# 884.net
KiCad netlist of a schematic drawn in EAGLE
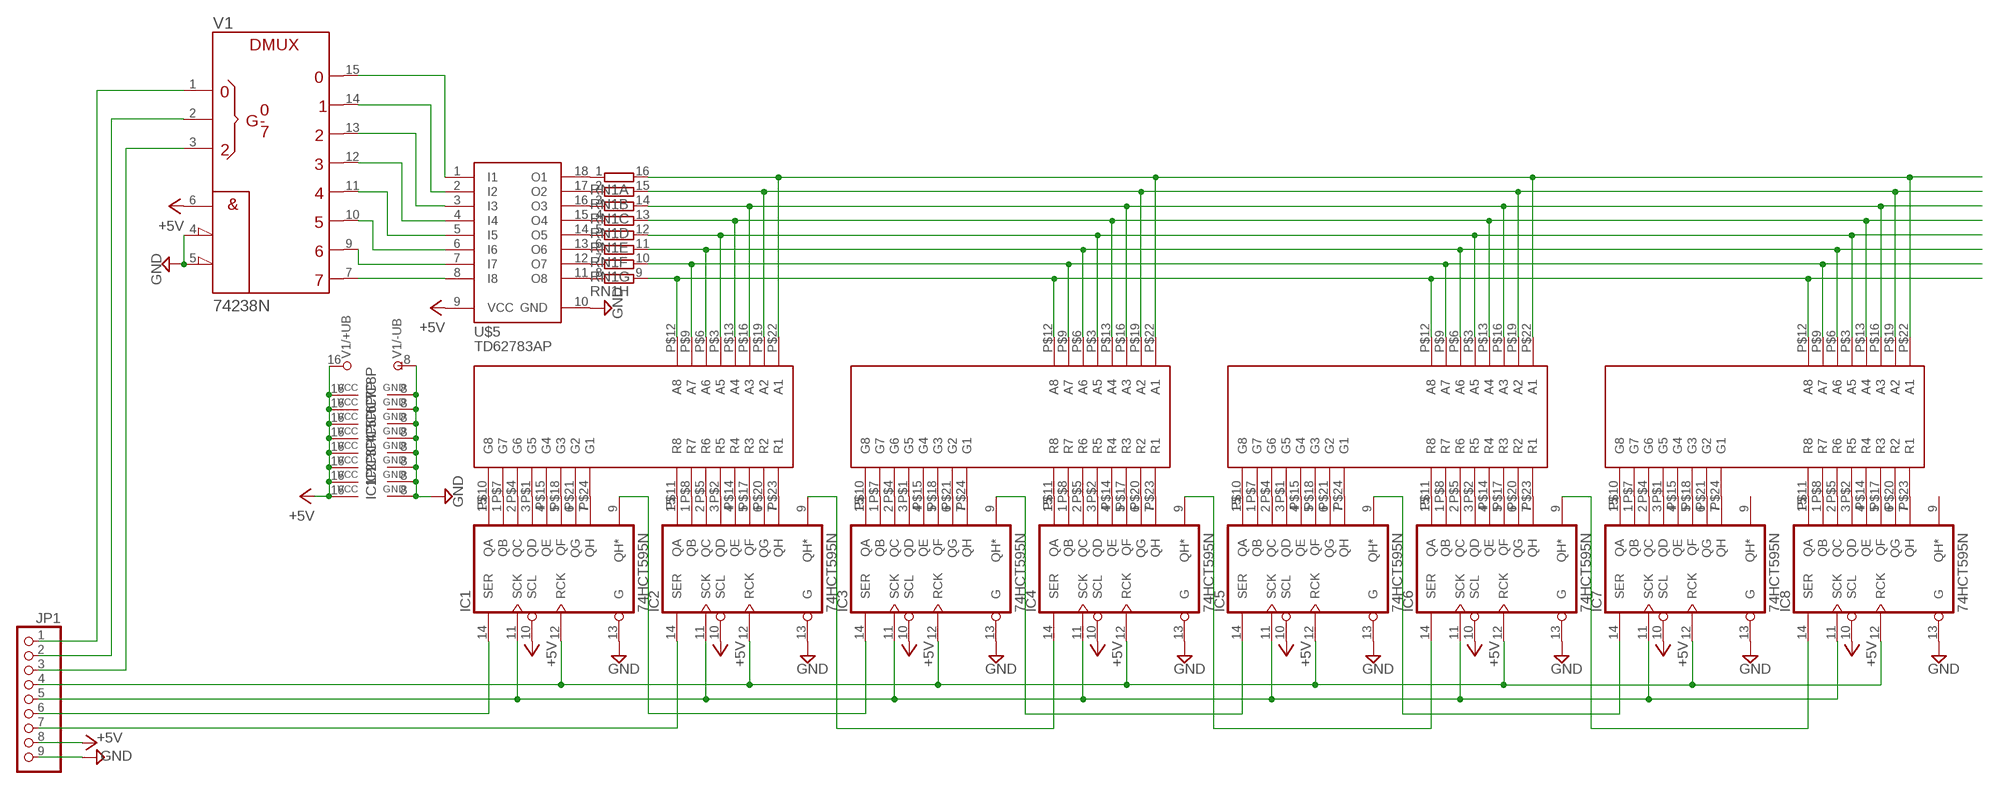
[diagram p0: schematic, sheet 1]

(export (version "E")
  (design (tool "Eeschema 10.0.6"))
  (components
    (comp (ref "IC1")
      (value "74HCT595N")
      (footprint "eagle-import:DIL16")
      (libsource (lib "eagle-import") (part "74595NHCT"))
    )
    (comp (ref "IC2")
      (value "74HCT595N")
      (footprint "eagle-import:DIL16")
      (libsource (lib "eagle-import") (part "74595NHCT"))
    )
    (comp (ref "IC3")
      (value "74HCT595N")
      (footprint "eagle-import:DIL16")
      (libsource (lib "eagle-import") (part "74595NHCT"))
    )
    (comp (ref "IC4")
      (value "74HCT595N")
      (footprint "eagle-import:DIL16")
      (libsource (lib "eagle-import") (part "74595NHCT"))
    )
    (comp (ref "IC5")
      (value "74HCT595N")
      (footprint "eagle-import:DIL16")
      (libsource (lib "eagle-import") (part "74595NHCT"))
    )
    (comp (ref "IC6")
      (value "74HCT595N")
      (footprint "eagle-import:DIL16")
      (libsource (lib "eagle-import") (part "74595NHCT"))
    )
    (comp (ref "IC7")
      (value "74HCT595N")
      (footprint "eagle-import:DIL16")
      (libsource (lib "eagle-import") (part "74595NHCT"))
    )
    (comp (ref "IC8")
      (value "74HCT595N")
      (footprint "eagle-import:DIL16")
      (libsource (lib "eagle-import") (part "74595NHCT"))
    )
    (comp (ref "JP1")
      (value "PINHD-1X9")
      (footprint "eagle-import:1X09")
      (libsource (lib "eagle-import") (part "PINHD-1X9"))
    )
    (comp (ref "RN1")
      (value "8R-N")
      (footprint "eagle-import:DIL16")
      (libsource (lib "eagle-import") (part "8R-N"))
    )
    (comp (ref "U$1")
      (value "LED_ARRAY_8X8")
      (footprint "eagle-import:2.54_11-24")
      (libsource (lib "eagle-import") (part "LED_ARRAY_8X8"))
    )
    (comp (ref "U$2")
      (value "LED_ARRAY_8X8")
      (footprint "eagle-import:2.54_11-24")
      (libsource (lib "eagle-import") (part "LED_ARRAY_8X8"))
    )
    (comp (ref "U$3")
      (value "LED_ARRAY_8X8")
      (footprint "eagle-import:2.54_11-24")
      (libsource (lib "eagle-import") (part "LED_ARRAY_8X8"))
    )
    (comp (ref "U$4")
      (value "LED_ARRAY_8X8")
      (footprint "eagle-import:2.54_11-24")
      (libsource (lib "eagle-import") (part "LED_ARRAY_8X8"))
    )
    (comp (ref "U$5")
      (value "TD62783AP")
      (footprint "eagle-import:DIL18")
      (libsource (lib "eagle-import") (part "TD62783AP"))
    )
    (comp (ref "V1")
      (value "74238N")
      (footprint "eagle-import:DIL16")
      (libsource (lib "eagle-import") (part "74238N"))
    )
  )
  (nets
    (net (code "1") (name "+5V") (class "Default")
      (node (ref "IC1") (pin "10") (pinfunction "SCL_10") (pintype "input"))
      (node (ref "IC1") (pin "16") (pinfunction "VCC_16") (pintype "power_in"))
      (node (ref "IC2") (pin "10") (pinfunction "SCL_10") (pintype "input"))
      (node (ref "IC2") (pin "16") (pinfunction "VCC_16") (pintype "power_in"))
      (node (ref "IC3") (pin "10") (pinfunction "SCL_10") (pintype "input"))
      (node (ref "IC3") (pin "16") (pinfunction "VCC_16") (pintype "power_in"))
      (node (ref "IC4") (pin "10") (pinfunction "SCL_10") (pintype "input"))
      (node (ref "IC4") (pin "16") (pinfunction "VCC_16") (pintype "power_in"))
      (node (ref "IC5") (pin "10") (pinfunction "SCL_10") (pintype "input"))
      (node (ref "IC5") (pin "16") (pinfunction "VCC_16") (pintype "power_in"))
      (node (ref "IC6") (pin "10") (pinfunction "SCL_10") (pintype "input"))
      (node (ref "IC6") (pin "16") (pinfunction "VCC_16") (pintype "power_in"))
      (node (ref "IC7") (pin "10") (pinfunction "SCL_10") (pintype "input"))
      (node (ref "IC7") (pin "16") (pinfunction "VCC_16") (pintype "power_in"))
      (node (ref "IC8") (pin "10") (pinfunction "SCL_10") (pintype "input"))
      (node (ref "IC8") (pin "16") (pinfunction "VCC_16") (pintype "power_in"))
      (node (ref "JP1") (pin "8") (pinfunction "8_8") (pintype "passive"))
      (node (ref "U$5") (pin "9") (pinfunction "VCC_9") (pintype "power_in"))
      (node (ref "V1") (pin "16") (pinfunction "+UB_16") (pintype "power_in"))
      (node (ref "V1") (pin "6") (pinfunction "G1_6") (pintype "input"))
    )
    (net (code "2") (name "GND") (class "Default")
      (node (ref "IC1") (pin "13") (pinfunction "G_13") (pintype "input"))
      (node (ref "IC1") (pin "8") (pinfunction "GND_8") (pintype "power_in"))
      (node (ref "IC2") (pin "13") (pinfunction "G_13") (pintype "input"))
      (node (ref "IC2") (pin "8") (pinfunction "GND_8") (pintype "power_in"))
      (node (ref "IC3") (pin "13") (pinfunction "G_13") (pintype "input"))
      (node (ref "IC3") (pin "8") (pinfunction "GND_8") (pintype "power_in"))
      (node (ref "IC4") (pin "13") (pinfunction "G_13") (pintype "input"))
      (node (ref "IC4") (pin "8") (pinfunction "GND_8") (pintype "power_in"))
      (node (ref "IC5") (pin "13") (pinfunction "G_13") (pintype "input"))
      (node (ref "IC5") (pin "8") (pinfunction "GND_8") (pintype "power_in"))
      (node (ref "IC6") (pin "13") (pinfunction "G_13") (pintype "input"))
      (node (ref "IC6") (pin "8") (pinfunction "GND_8") (pintype "power_in"))
      (node (ref "IC7") (pin "13") (pinfunction "G_13") (pintype "input"))
      (node (ref "IC7") (pin "8") (pinfunction "GND_8") (pintype "power_in"))
      (node (ref "IC8") (pin "13") (pinfunction "G_13") (pintype "input"))
      (node (ref "IC8") (pin "8") (pinfunction "GND_8") (pintype "power_in"))
      (node (ref "JP1") (pin "9") (pinfunction "9_9") (pintype "passive"))
      (node (ref "U$5") (pin "10") (pinfunction "GND_10") (pintype "power_in"))
      (node (ref "V1") (pin "4") (pinfunction "~{G2A}_4") (pintype "input"))
      (node (ref "V1") (pin "5") (pinfunction "~{G2B}_5") (pintype "input"))
      (node (ref "V1") (pin "8") (pinfunction "-UB_8") (pintype "power_in"))
    )
    (net (code "3") (name "Net-(IC1A-QA)") (class "Default")
      (node (ref "IC1") (pin "15") (pinfunction "QA_15") (pintype "tri_state"))
      (node (ref "U$1") (pin "P$10") (pinfunction "G8_P$10") (pintype "bidirectional"))
    )
    (net (code "4") (name "Net-(IC1A-QB)") (class "Default")
      (node (ref "IC1") (pin "1") (pinfunction "QB_1") (pintype "tri_state"))
      (node (ref "U$1") (pin "P$7") (pinfunction "G7_P$7") (pintype "bidirectional"))
    )
    (net (code "5") (name "Net-(IC1A-QC)") (class "Default")
      (node (ref "IC1") (pin "2") (pinfunction "QC_2") (pintype "tri_state"))
      (node (ref "U$1") (pin "P$4") (pinfunction "G6_P$4") (pintype "bidirectional"))
    )
    (net (code "6") (name "Net-(IC1A-QD)") (class "Default")
      (node (ref "IC1") (pin "3") (pinfunction "QD_3") (pintype "tri_state"))
      (node (ref "U$1") (pin "P$1") (pinfunction "G5_P$1") (pintype "bidirectional"))
    )
    (net (code "7") (name "Net-(IC1A-QE)") (class "Default")
      (node (ref "IC1") (pin "4") (pinfunction "QE_4") (pintype "tri_state"))
      (node (ref "U$1") (pin "P$15") (pinfunction "G4_P$15") (pintype "bidirectional"))
    )
    (net (code "8") (name "Net-(IC1A-QF)") (class "Default")
      (node (ref "IC1") (pin "5") (pinfunction "QF_5") (pintype "tri_state"))
      (node (ref "U$1") (pin "P$18") (pinfunction "G3_P$18") (pintype "bidirectional"))
    )
    (net (code "9") (name "Net-(IC1A-QG)") (class "Default")
      (node (ref "IC1") (pin "6") (pinfunction "QG_6") (pintype "tri_state"))
      (node (ref "U$1") (pin "P$21") (pinfunction "G2_P$21") (pintype "bidirectional"))
    )
    (net (code "10") (name "Net-(IC1A-QH)") (class "Default")
      (node (ref "IC1") (pin "7") (pinfunction "QH_7") (pintype "tri_state"))
      (node (ref "U$1") (pin "P$24") (pinfunction "G1_P$24") (pintype "bidirectional"))
    )
    (net (code "11") (name "Net-(IC1A-QH*)") (class "Default")
      (node (ref "IC1") (pin "9") (pinfunction "QH*_9") (pintype "tri_state"))
      (node (ref "IC3") (pin "14") (pinfunction "SER_14") (pintype "input"))
    )
    (net (code "12") (name "Net-(IC1A-RCK)") (class "Default")
      (node (ref "IC1") (pin "12") (pinfunction "RCK_12") (pintype "input"))
      (node (ref "IC2") (pin "12") (pinfunction "RCK_12") (pintype "input"))
      (node (ref "IC3") (pin "12") (pinfunction "RCK_12") (pintype "input"))
      (node (ref "IC4") (pin "12") (pinfunction "RCK_12") (pintype "input"))
      (node (ref "IC5") (pin "12") (pinfunction "RCK_12") (pintype "input"))
      (node (ref "IC6") (pin "12") (pinfunction "RCK_12") (pintype "input"))
      (node (ref "IC7") (pin "12") (pinfunction "RCK_12") (pintype "input"))
      (node (ref "IC8") (pin "12") (pinfunction "RCK_12") (pintype "input"))
      (node (ref "JP1") (pin "4") (pinfunction "4_4") (pintype "passive"))
    )
    (net (code "13") (name "Net-(IC1A-SCK)") (class "Default")
      (node (ref "IC1") (pin "11") (pinfunction "SCK_11") (pintype "input"))
      (node (ref "IC2") (pin "11") (pinfunction "SCK_11") (pintype "input"))
      (node (ref "IC3") (pin "11") (pinfunction "SCK_11") (pintype "input"))
      (node (ref "IC4") (pin "11") (pinfunction "SCK_11") (pintype "input"))
      (node (ref "IC5") (pin "11") (pinfunction "SCK_11") (pintype "input"))
      (node (ref "IC6") (pin "11") (pinfunction "SCK_11") (pintype "input"))
      (node (ref "IC7") (pin "11") (pinfunction "SCK_11") (pintype "input"))
      (node (ref "IC8") (pin "11") (pinfunction "SCK_11") (pintype "input"))
      (node (ref "JP1") (pin "5") (pinfunction "5_5") (pintype "passive"))
    )
    (net (code "14") (name "Net-(IC1A-SER)") (class "Default")
      (node (ref "IC1") (pin "14") (pinfunction "SER_14") (pintype "input"))
      (node (ref "JP1") (pin "6") (pinfunction "6_6") (pintype "passive"))
    )
    (net (code "15") (name "Net-(IC2A-QA)") (class "Default")
      (node (ref "IC2") (pin "15") (pinfunction "QA_15") (pintype "tri_state"))
      (node (ref "U$1") (pin "P$11") (pinfunction "R8_P$11") (pintype "bidirectional"))
    )
    (net (code "16") (name "Net-(IC2A-QB)") (class "Default")
      (node (ref "IC2") (pin "1") (pinfunction "QB_1") (pintype "tri_state"))
      (node (ref "U$1") (pin "P$8") (pinfunction "R7_P$8") (pintype "bidirectional"))
    )
    (net (code "17") (name "Net-(IC2A-QC)") (class "Default")
      (node (ref "IC2") (pin "2") (pinfunction "QC_2") (pintype "tri_state"))
      (node (ref "U$1") (pin "P$5") (pinfunction "R6_P$5") (pintype "bidirectional"))
    )
    (net (code "18") (name "Net-(IC2A-QD)") (class "Default")
      (node (ref "IC2") (pin "3") (pinfunction "QD_3") (pintype "tri_state"))
      (node (ref "U$1") (pin "P$2") (pinfunction "R5_P$2") (pintype "bidirectional"))
    )
    (net (code "19") (name "Net-(IC2A-QE)") (class "Default")
      (node (ref "IC2") (pin "4") (pinfunction "QE_4") (pintype "tri_state"))
      (node (ref "U$1") (pin "P$14") (pinfunction "R4_P$14") (pintype "bidirectional"))
    )
    (net (code "20") (name "Net-(IC2A-QF)") (class "Default")
      (node (ref "IC2") (pin "5") (pinfunction "QF_5") (pintype "tri_state"))
      (node (ref "U$1") (pin "P$17") (pinfunction "R3_P$17") (pintype "bidirectional"))
    )
    (net (code "21") (name "Net-(IC2A-QG)") (class "Default")
      (node (ref "IC2") (pin "6") (pinfunction "QG_6") (pintype "tri_state"))
      (node (ref "U$1") (pin "P$20") (pinfunction "R2_P$20") (pintype "bidirectional"))
    )
    (net (code "22") (name "Net-(IC2A-QH)") (class "Default")
      (node (ref "IC2") (pin "7") (pinfunction "QH_7") (pintype "tri_state"))
      (node (ref "U$1") (pin "P$23") (pinfunction "R1_P$23") (pintype "bidirectional"))
    )
    (net (code "23") (name "Net-(IC2A-QH*)") (class "Default")
      (node (ref "IC2") (pin "9") (pinfunction "QH*_9") (pintype "tri_state"))
      (node (ref "IC4") (pin "14") (pinfunction "SER_14") (pintype "input"))
    )
    (net (code "24") (name "Net-(IC2A-SER)") (class "Default")
      (node (ref "IC2") (pin "14") (pinfunction "SER_14") (pintype "input"))
      (node (ref "JP1") (pin "7") (pinfunction "7_7") (pintype "passive"))
    )
    (net (code "25") (name "Net-(IC3A-QA)") (class "Default")
      (node (ref "IC3") (pin "15") (pinfunction "QA_15") (pintype "tri_state"))
      (node (ref "U$2") (pin "P$10") (pinfunction "G8_P$10") (pintype "bidirectional"))
    )
    (net (code "26") (name "Net-(IC3A-QB)") (class "Default")
      (node (ref "IC3") (pin "1") (pinfunction "QB_1") (pintype "tri_state"))
      (node (ref "U$2") (pin "P$7") (pinfunction "G7_P$7") (pintype "bidirectional"))
    )
    (net (code "27") (name "Net-(IC3A-QC)") (class "Default")
      (node (ref "IC3") (pin "2") (pinfunction "QC_2") (pintype "tri_state"))
      (node (ref "U$2") (pin "P$4") (pinfunction "G6_P$4") (pintype "bidirectional"))
    )
    (net (code "28") (name "Net-(IC3A-QD)") (class "Default")
      (node (ref "IC3") (pin "3") (pinfunction "QD_3") (pintype "tri_state"))
      (node (ref "U$2") (pin "P$1") (pinfunction "G5_P$1") (pintype "bidirectional"))
    )
    (net (code "29") (name "Net-(IC3A-QE)") (class "Default")
      (node (ref "IC3") (pin "4") (pinfunction "QE_4") (pintype "tri_state"))
      (node (ref "U$2") (pin "P$15") (pinfunction "G4_P$15") (pintype "bidirectional"))
    )
    (net (code "30") (name "Net-(IC3A-QF)") (class "Default")
      (node (ref "IC3") (pin "5") (pinfunction "QF_5") (pintype "tri_state"))
      (node (ref "U$2") (pin "P$18") (pinfunction "G3_P$18") (pintype "bidirectional"))
    )
    (net (code "31") (name "Net-(IC3A-QG)") (class "Default")
      (node (ref "IC3") (pin "6") (pinfunction "QG_6") (pintype "tri_state"))
      (node (ref "U$2") (pin "P$21") (pinfunction "G2_P$21") (pintype "bidirectional"))
    )
    (net (code "32") (name "Net-(IC3A-QH)") (class "Default")
      (node (ref "IC3") (pin "7") (pinfunction "QH_7") (pintype "tri_state"))
      (node (ref "U$2") (pin "P$24") (pinfunction "G1_P$24") (pintype "bidirectional"))
    )
    (net (code "33") (name "Net-(IC3A-QH*)") (class "Default")
      (node (ref "IC3") (pin "9") (pinfunction "QH*_9") (pintype "tri_state"))
      (node (ref "IC5") (pin "14") (pinfunction "SER_14") (pintype "input"))
    )
    (net (code "34") (name "Net-(IC4A-QA)") (class "Default")
      (node (ref "IC4") (pin "15") (pinfunction "QA_15") (pintype "tri_state"))
      (node (ref "U$2") (pin "P$11") (pinfunction "R8_P$11") (pintype "bidirectional"))
    )
    (net (code "35") (name "Net-(IC4A-QB)") (class "Default")
      (node (ref "IC4") (pin "1") (pinfunction "QB_1") (pintype "tri_state"))
      (node (ref "U$2") (pin "P$8") (pinfunction "R7_P$8") (pintype "bidirectional"))
    )
    (net (code "36") (name "Net-(IC4A-QC)") (class "Default")
      (node (ref "IC4") (pin "2") (pinfunction "QC_2") (pintype "tri_state"))
      (node (ref "U$2") (pin "P$5") (pinfunction "R6_P$5") (pintype "bidirectional"))
    )
    (net (code "37") (name "Net-(IC4A-QD)") (class "Default")
      (node (ref "IC4") (pin "3") (pinfunction "QD_3") (pintype "tri_state"))
      (node (ref "U$2") (pin "P$2") (pinfunction "R5_P$2") (pintype "bidirectional"))
    )
    (net (code "38") (name "Net-(IC4A-QE)") (class "Default")
      (node (ref "IC4") (pin "4") (pinfunction "QE_4") (pintype "tri_state"))
      (node (ref "U$2") (pin "P$14") (pinfunction "R4_P$14") (pintype "bidirectional"))
    )
    (net (code "39") (name "Net-(IC4A-QF)") (class "Default")
      (node (ref "IC4") (pin "5") (pinfunction "QF_5") (pintype "tri_state"))
      (node (ref "U$2") (pin "P$17") (pinfunction "R3_P$17") (pintype "bidirectional"))
    )
    (net (code "40") (name "Net-(IC4A-QG)") (class "Default")
      (node (ref "IC4") (pin "6") (pinfunction "QG_6") (pintype "tri_state"))
      (node (ref "U$2") (pin "P$20") (pinfunction "R2_P$20") (pintype "bidirectional"))
    )
    (net (code "41") (name "Net-(IC4A-QH)") (class "Default")
      (node (ref "IC4") (pin "7") (pinfunction "QH_7") (pintype "tri_state"))
      (node (ref "U$2") (pin "P$23") (pinfunction "R1_P$23") (pintype "bidirectional"))
    )
    (net (code "42") (name "Net-(IC4A-QH*)") (class "Default")
      (node (ref "IC4") (pin "9") (pinfunction "QH*_9") (pintype "tri_state"))
      (node (ref "IC6") (pin "14") (pinfunction "SER_14") (pintype "input"))
    )
    (net (code "43") (name "Net-(IC5A-QA)") (class "Default")
      (node (ref "IC5") (pin "15") (pinfunction "QA_15") (pintype "tri_state"))
      (node (ref "U$3") (pin "P$10") (pinfunction "G8_P$10") (pintype "bidirectional"))
    )
    (net (code "44") (name "Net-(IC5A-QB)") (class "Default")
      (node (ref "IC5") (pin "1") (pinfunction "QB_1") (pintype "tri_state"))
      (node (ref "U$3") (pin "P$7") (pinfunction "G7_P$7") (pintype "bidirectional"))
    )
    (net (code "45") (name "Net-(IC5A-QC)") (class "Default")
      (node (ref "IC5") (pin "2") (pinfunction "QC_2") (pintype "tri_state"))
      (node (ref "U$3") (pin "P$4") (pinfunction "G6_P$4") (pintype "bidirectional"))
    )
    (net (code "46") (name "Net-(IC5A-QD)") (class "Default")
      (node (ref "IC5") (pin "3") (pinfunction "QD_3") (pintype "tri_state"))
      (node (ref "U$3") (pin "P$1") (pinfunction "G5_P$1") (pintype "bidirectional"))
    )
    (net (code "47") (name "Net-(IC5A-QE)") (class "Default")
      (node (ref "IC5") (pin "4") (pinfunction "QE_4") (pintype "tri_state"))
      (node (ref "U$3") (pin "P$15") (pinfunction "G4_P$15") (pintype "bidirectional"))
    )
    (net (code "48") (name "Net-(IC5A-QF)") (class "Default")
      (node (ref "IC5") (pin "5") (pinfunction "QF_5") (pintype "tri_state"))
      (node (ref "U$3") (pin "P$18") (pinfunction "G3_P$18") (pintype "bidirectional"))
    )
    (net (code "49") (name "Net-(IC5A-QG)") (class "Default")
      (node (ref "IC5") (pin "6") (pinfunction "QG_6") (pintype "tri_state"))
      (node (ref "U$3") (pin "P$21") (pinfunction "G2_P$21") (pintype "bidirectional"))
    )
    (net (code "50") (name "Net-(IC5A-QH)") (class "Default")
      (node (ref "IC5") (pin "7") (pinfunction "QH_7") (pintype "tri_state"))
      (node (ref "U$3") (pin "P$24") (pinfunction "G1_P$24") (pintype "bidirectional"))
    )
    (net (code "51") (name "Net-(IC5A-QH*)") (class "Default")
      (node (ref "IC5") (pin "9") (pinfunction "QH*_9") (pintype "tri_state"))
      (node (ref "IC7") (pin "14") (pinfunction "SER_14") (pintype "input"))
    )
    (net (code "52") (name "Net-(IC6A-QA)") (class "Default")
      (node (ref "IC6") (pin "15") (pinfunction "QA_15") (pintype "tri_state"))
      (node (ref "U$3") (pin "P$11") (pinfunction "R8_P$11") (pintype "bidirectional"))
    )
    (net (code "53") (name "Net-(IC6A-QB)") (class "Default")
      (node (ref "IC6") (pin "1") (pinfunction "QB_1") (pintype "tri_state"))
      (node (ref "U$3") (pin "P$8") (pinfunction "R7_P$8") (pintype "bidirectional"))
    )
    (net (code "54") (name "Net-(IC6A-QC)") (class "Default")
      (node (ref "IC6") (pin "2") (pinfunction "QC_2") (pintype "tri_state"))
      (node (ref "U$3") (pin "P$5") (pinfunction "R6_P$5") (pintype "bidirectional"))
    )
    (net (code "55") (name "Net-(IC6A-QD)") (class "Default")
      (node (ref "IC6") (pin "3") (pinfunction "QD_3") (pintype "tri_state"))
      (node (ref "U$3") (pin "P$2") (pinfunction "R5_P$2") (pintype "bidirectional"))
    )
    (net (code "56") (name "Net-(IC6A-QE)") (class "Default")
      (node (ref "IC6") (pin "4") (pinfunction "QE_4") (pintype "tri_state"))
      (node (ref "U$3") (pin "P$14") (pinfunction "R4_P$14") (pintype "bidirectional"))
    )
    (net (code "57") (name "Net-(IC6A-QF)") (class "Default")
      (node (ref "IC6") (pin "5") (pinfunction "QF_5") (pintype "tri_state"))
      (node (ref "U$3") (pin "P$17") (pinfunction "R3_P$17") (pintype "bidirectional"))
    )
    (net (code "58") (name "Net-(IC6A-QG)") (class "Default")
      (node (ref "IC6") (pin "6") (pinfunction "QG_6") (pintype "tri_state"))
      (node (ref "U$3") (pin "P$20") (pinfunction "R2_P$20") (pintype "bidirectional"))
    )
    (net (code "59") (name "Net-(IC6A-QH)") (class "Default")
      (node (ref "IC6") (pin "7") (pinfunction "QH_7") (pintype "tri_state"))
      (node (ref "U$3") (pin "P$23") (pinfunction "R1_P$23") (pintype "bidirectional"))
    )
    (net (code "60") (name "Net-(IC6A-QH*)") (class "Default")
      (node (ref "IC6") (pin "9") (pinfunction "QH*_9") (pintype "tri_state"))
      (node (ref "IC8") (pin "14") (pinfunction "SER_14") (pintype "input"))
    )
    (net (code "61") (name "Net-(IC7A-QA)") (class "Default")
      (node (ref "IC7") (pin "15") (pinfunction "QA_15") (pintype "tri_state"))
      (node (ref "U$4") (pin "P$10") (pinfunction "G8_P$10") (pintype "bidirectional"))
    )
    (net (code "62") (name "Net-(IC7A-QB)") (class "Default")
      (node (ref "IC7") (pin "1") (pinfunction "QB_1") (pintype "tri_state"))
      (node (ref "U$4") (pin "P$7") (pinfunction "G7_P$7") (pintype "bidirectional"))
    )
    (net (code "63") (name "Net-(IC7A-QC)") (class "Default")
      (node (ref "IC7") (pin "2") (pinfunction "QC_2") (pintype "tri_state"))
      (node (ref "U$4") (pin "P$4") (pinfunction "G6_P$4") (pintype "bidirectional"))
    )
    (net (code "64") (name "Net-(IC7A-QD)") (class "Default")
      (node (ref "IC7") (pin "3") (pinfunction "QD_3") (pintype "tri_state"))
      (node (ref "U$4") (pin "P$1") (pinfunction "G5_P$1") (pintype "bidirectional"))
    )
    (net (code "65") (name "Net-(IC7A-QE)") (class "Default")
      (node (ref "IC7") (pin "4") (pinfunction "QE_4") (pintype "tri_state"))
      (node (ref "U$4") (pin "P$15") (pinfunction "G4_P$15") (pintype "bidirectional"))
    )
    (net (code "66") (name "Net-(IC7A-QF)") (class "Default")
      (node (ref "IC7") (pin "5") (pinfunction "QF_5") (pintype "tri_state"))
      (node (ref "U$4") (pin "P$18") (pinfunction "G3_P$18") (pintype "bidirectional"))
    )
    (net (code "67") (name "Net-(IC7A-QG)") (class "Default")
      (node (ref "IC7") (pin "6") (pinfunction "QG_6") (pintype "tri_state"))
      (node (ref "U$4") (pin "P$21") (pinfunction "G2_P$21") (pintype "bidirectional"))
    )
    (net (code "68") (name "Net-(IC7A-QH)") (class "Default")
      (node (ref "IC7") (pin "7") (pinfunction "QH_7") (pintype "tri_state"))
      (node (ref "U$4") (pin "P$24") (pinfunction "G1_P$24") (pintype "bidirectional"))
    )
    (net (code "69") (name "Net-(IC8A-QA)") (class "Default")
      (node (ref "IC8") (pin "15") (pinfunction "QA_15") (pintype "tri_state"))
      (node (ref "U$4") (pin "P$11") (pinfunction "R8_P$11") (pintype "bidirectional"))
    )
    (net (code "70") (name "Net-(IC8A-QB)") (class "Default")
      (node (ref "IC8") (pin "1") (pinfunction "QB_1") (pintype "tri_state"))
      (node (ref "U$4") (pin "P$8") (pinfunction "R7_P$8") (pintype "bidirectional"))
    )
    (net (code "71") (name "Net-(IC8A-QC)") (class "Default")
      (node (ref "IC8") (pin "2") (pinfunction "QC_2") (pintype "tri_state"))
      (node (ref "U$4") (pin "P$5") (pinfunction "R6_P$5") (pintype "bidirectional"))
    )
    (net (code "72") (name "Net-(IC8A-QD)") (class "Default")
      (node (ref "IC8") (pin "3") (pinfunction "QD_3") (pintype "tri_state"))
      (node (ref "U$4") (pin "P$2") (pinfunction "R5_P$2") (pintype "bidirectional"))
    )
    (net (code "73") (name "Net-(IC8A-QE)") (class "Default")
      (node (ref "IC8") (pin "4") (pinfunction "QE_4") (pintype "tri_state"))
      (node (ref "U$4") (pin "P$14") (pinfunction "R4_P$14") (pintype "bidirectional"))
    )
    (net (code "74") (name "Net-(IC8A-QF)") (class "Default")
      (node (ref "IC8") (pin "5") (pinfunction "QF_5") (pintype "tri_state"))
      (node (ref "U$4") (pin "P$17") (pinfunction "R3_P$17") (pintype "bidirectional"))
    )
    (net (code "75") (name "Net-(IC8A-QG)") (class "Default")
      (node (ref "IC8") (pin "6") (pinfunction "QG_6") (pintype "tri_state"))
      (node (ref "U$4") (pin "P$20") (pinfunction "R2_P$20") (pintype "bidirectional"))
    )
    (net (code "76") (name "Net-(IC8A-QH)") (class "Default")
      (node (ref "IC8") (pin "7") (pinfunction "QH_7") (pintype "tri_state"))
      (node (ref "U$4") (pin "P$23") (pinfunction "R1_P$23") (pintype "bidirectional"))
    )
    (net (code "77") (name "Net-(RN1A-2)") (class "Default")
      (node (ref "RN1") (pin "16") (pinfunction "2_16") (pintype "passive"))
      (node (ref "U$1") (pin "P$22") (pinfunction "A1_P$22") (pintype "bidirectional"))
      (node (ref "U$2") (pin "P$22") (pinfunction "A1_P$22") (pintype "bidirectional"))
      (node (ref "U$3") (pin "P$22") (pinfunction "A1_P$22") (pintype "bidirectional"))
      (node (ref "U$4") (pin "P$22") (pinfunction "A1_P$22") (pintype "bidirectional"))
    )
    (net (code "78") (name "Net-(RN1B-1)") (class "Default")
      (node (ref "RN1") (pin "2") (pinfunction "1_2") (pintype "passive"))
      (node (ref "U$5") (pin "17") (pinfunction "O2_17") (pintype "output"))
    )
    (net (code "79") (name "Net-(RN1B-2)") (class "Default")
      (node (ref "RN1") (pin "15") (pinfunction "2_15") (pintype "passive"))
      (node (ref "U$1") (pin "P$19") (pinfunction "A2_P$19") (pintype "bidirectional"))
      (node (ref "U$2") (pin "P$19") (pinfunction "A2_P$19") (pintype "bidirectional"))
      (node (ref "U$3") (pin "P$19") (pinfunction "A2_P$19") (pintype "bidirectional"))
      (node (ref "U$4") (pin "P$19") (pinfunction "A2_P$19") (pintype "bidirectional"))
    )
    (net (code "80") (name "Net-(RN1C-1)") (class "Default")
      (node (ref "RN1") (pin "3") (pinfunction "1_3") (pintype "passive"))
      (node (ref "U$5") (pin "16") (pinfunction "O3_16") (pintype "output"))
    )
    (net (code "81") (name "Net-(RN1C-2)") (class "Default")
      (node (ref "RN1") (pin "14") (pinfunction "2_14") (pintype "passive"))
      (node (ref "U$1") (pin "P$16") (pinfunction "A3_P$16") (pintype "bidirectional"))
      (node (ref "U$2") (pin "P$16") (pinfunction "A3_P$16") (pintype "bidirectional"))
      (node (ref "U$3") (pin "P$16") (pinfunction "A3_P$16") (pintype "bidirectional"))
      (node (ref "U$4") (pin "P$16") (pinfunction "A3_P$16") (pintype "bidirectional"))
    )
    (net (code "82") (name "Net-(RN1D-1)") (class "Default")
      (node (ref "RN1") (pin "4") (pinfunction "1_4") (pintype "passive"))
      (node (ref "U$5") (pin "15") (pinfunction "O4_15") (pintype "output"))
    )
    (net (code "83") (name "Net-(RN1D-2)") (class "Default")
      (node (ref "RN1") (pin "13") (pinfunction "2_13") (pintype "passive"))
      (node (ref "U$1") (pin "P$13") (pinfunction "A4_P$13") (pintype "bidirectional"))
      (node (ref "U$2") (pin "P$13") (pinfunction "A4_P$13") (pintype "bidirectional"))
      (node (ref "U$3") (pin "P$13") (pinfunction "A4_P$13") (pintype "bidirectional"))
      (node (ref "U$4") (pin "P$13") (pinfunction "A4_P$13") (pintype "bidirectional"))
    )
    (net (code "84") (name "Net-(RN1E-1)") (class "Default")
      (node (ref "RN1") (pin "5") (pinfunction "1_5") (pintype "passive"))
      (node (ref "U$5") (pin "14") (pinfunction "O5_14") (pintype "output"))
    )
    (net (code "85") (name "Net-(RN1E-2)") (class "Default")
      (node (ref "RN1") (pin "12") (pinfunction "2_12") (pintype "passive"))
      (node (ref "U$1") (pin "P$3") (pinfunction "A5_P$3") (pintype "bidirectional"))
      (node (ref "U$2") (pin "P$3") (pinfunction "A5_P$3") (pintype "bidirectional"))
      (node (ref "U$3") (pin "P$3") (pinfunction "A5_P$3") (pintype "bidirectional"))
      (node (ref "U$4") (pin "P$3") (pinfunction "A5_P$3") (pintype "bidirectional"))
    )
    (net (code "86") (name "Net-(RN1F-1)") (class "Default")
      (node (ref "RN1") (pin "6") (pinfunction "1_6") (pintype "passive"))
      (node (ref "U$5") (pin "13") (pinfunction "O6_13") (pintype "output"))
    )
    (net (code "87") (name "Net-(RN1F-2)") (class "Default")
      (node (ref "RN1") (pin "11") (pinfunction "2_11") (pintype "passive"))
      (node (ref "U$1") (pin "P$6") (pinfunction "A6_P$6") (pintype "bidirectional"))
      (node (ref "U$2") (pin "P$6") (pinfunction "A6_P$6") (pintype "bidirectional"))
      (node (ref "U$3") (pin "P$6") (pinfunction "A6_P$6") (pintype "bidirectional"))
      (node (ref "U$4") (pin "P$6") (pinfunction "A6_P$6") (pintype "bidirectional"))
    )
    (net (code "88") (name "Net-(RN1G-1)") (class "Default")
      (node (ref "RN1") (pin "7") (pinfunction "1_7") (pintype "passive"))
      (node (ref "U$5") (pin "12") (pinfunction "O7_12") (pintype "output"))
    )
    (net (code "89") (name "Net-(RN1G-2)") (class "Default")
      (node (ref "RN1") (pin "10") (pinfunction "2_10") (pintype "passive"))
      (node (ref "U$1") (pin "P$9") (pinfunction "A7_P$9") (pintype "bidirectional"))
      (node (ref "U$2") (pin "P$9") (pinfunction "A7_P$9") (pintype "bidirectional"))
      (node (ref "U$3") (pin "P$9") (pinfunction "A7_P$9") (pintype "bidirectional"))
      (node (ref "U$4") (pin "P$9") (pinfunction "A7_P$9") (pintype "bidirectional"))
    )
    (net (code "90") (name "Net-(RN1H-1)") (class "Default")
      (node (ref "RN1") (pin "8") (pinfunction "1_8") (pintype "passive"))
      (node (ref "U$5") (pin "11") (pinfunction "O8_11") (pintype "output"))
    )
    (net (code "91") (name "Net-(RN1H-2)") (class "Default")
      (node (ref "RN1") (pin "9") (pinfunction "2_9") (pintype "passive"))
      (node (ref "U$1") (pin "P$12") (pinfunction "A8_P$12") (pintype "bidirectional"))
      (node (ref "U$2") (pin "P$12") (pinfunction "A8_P$12") (pintype "bidirectional"))
      (node (ref "U$3") (pin "P$12") (pinfunction "A8_P$12") (pintype "bidirectional"))
      (node (ref "U$4") (pin "P$12") (pinfunction "A8_P$12") (pintype "bidirectional"))
    )
    (net (code "92") (name "Net-(U$5-I1)") (class "Default")
      (node (ref "U$5") (pin "1") (pinfunction "I1_1") (pintype "input"))
      (node (ref "V1") (pin "15") (pinfunction "Y0_15") (pintype "output"))
    )
    (net (code "93") (name "Net-(U$5-I2)") (class "Default")
      (node (ref "U$5") (pin "2") (pinfunction "I2_2") (pintype "input"))
      (node (ref "V1") (pin "14") (pinfunction "Y1_14") (pintype "output"))
    )
    (net (code "94") (name "Net-(U$5-I3)") (class "Default")
      (node (ref "U$5") (pin "3") (pinfunction "I3_3") (pintype "input"))
      (node (ref "V1") (pin "13") (pinfunction "Y2_13") (pintype "output"))
    )
    (net (code "95") (name "Net-(U$5-I4)") (class "Default")
      (node (ref "U$5") (pin "4") (pinfunction "I4_4") (pintype "input"))
      (node (ref "V1") (pin "12") (pinfunction "Y3_12") (pintype "output"))
    )
    (net (code "96") (name "Net-(U$5-I5)") (class "Default")
      (node (ref "U$5") (pin "5") (pinfunction "I5_5") (pintype "input"))
      (node (ref "V1") (pin "11") (pinfunction "Y4_11") (pintype "output"))
    )
    (net (code "97") (name "Net-(U$5-I6)") (class "Default")
      (node (ref "U$5") (pin "6") (pinfunction "I6_6") (pintype "input"))
      (node (ref "V1") (pin "10") (pinfunction "Y5_10") (pintype "output"))
    )
    (net (code "98") (name "Net-(U$5-I7)") (class "Default")
      (node (ref "U$5") (pin "7") (pinfunction "I7_7") (pintype "input"))
      (node (ref "V1") (pin "9") (pinfunction "Y6_9") (pintype "output"))
    )
    (net (code "99") (name "Net-(U$5-I8)") (class "Default")
      (node (ref "U$5") (pin "8") (pinfunction "I8_8") (pintype "input"))
      (node (ref "V1") (pin "7") (pinfunction "Y7_7") (pintype "output"))
    )
    (net (code "100") (name "Net-(U$5-O1)") (class "Default")
      (node (ref "RN1") (pin "1") (pinfunction "1_1") (pintype "passive"))
      (node (ref "U$5") (pin "18") (pinfunction "O1_18") (pintype "output"))
    )
    (net (code "101") (name "Net-(V1C-A)") (class "Default")
      (node (ref "JP1") (pin "1") (pinfunction "1_1") (pintype "passive"))
      (node (ref "V1") (pin "1") (pinfunction "A_1") (pintype "input"))
    )
    (net (code "102") (name "Net-(V1C-B)") (class "Default")
      (node (ref "JP1") (pin "2") (pinfunction "2_2") (pintype "passive"))
      (node (ref "V1") (pin "2") (pinfunction "B_2") (pintype "input"))
    )
    (net (code "103") (name "Net-(V1C-C)") (class "Default")
      (node (ref "JP1") (pin "3") (pinfunction "3_3") (pintype "passive"))
      (node (ref "V1") (pin "3") (pinfunction "C_3") (pintype "input"))
    )
    (net (code "104") (name "unconnected-(IC7A-QH*-Pad9)") (class "Default")
      (node (ref "IC7") (pin "9") (pinfunction "QH*_9") (pintype "tri_state"))
    )
    (net (code "105") (name "unconnected-(IC8A-QH*-Pad9)") (class "Default")
      (node (ref "IC8") (pin "9") (pinfunction "QH*_9") (pintype "tri_state"))
    )
  )
)
